# openSX70_MEROE_V7_20190605.net
KiCad netlist of a schematic drawn in EAGLE
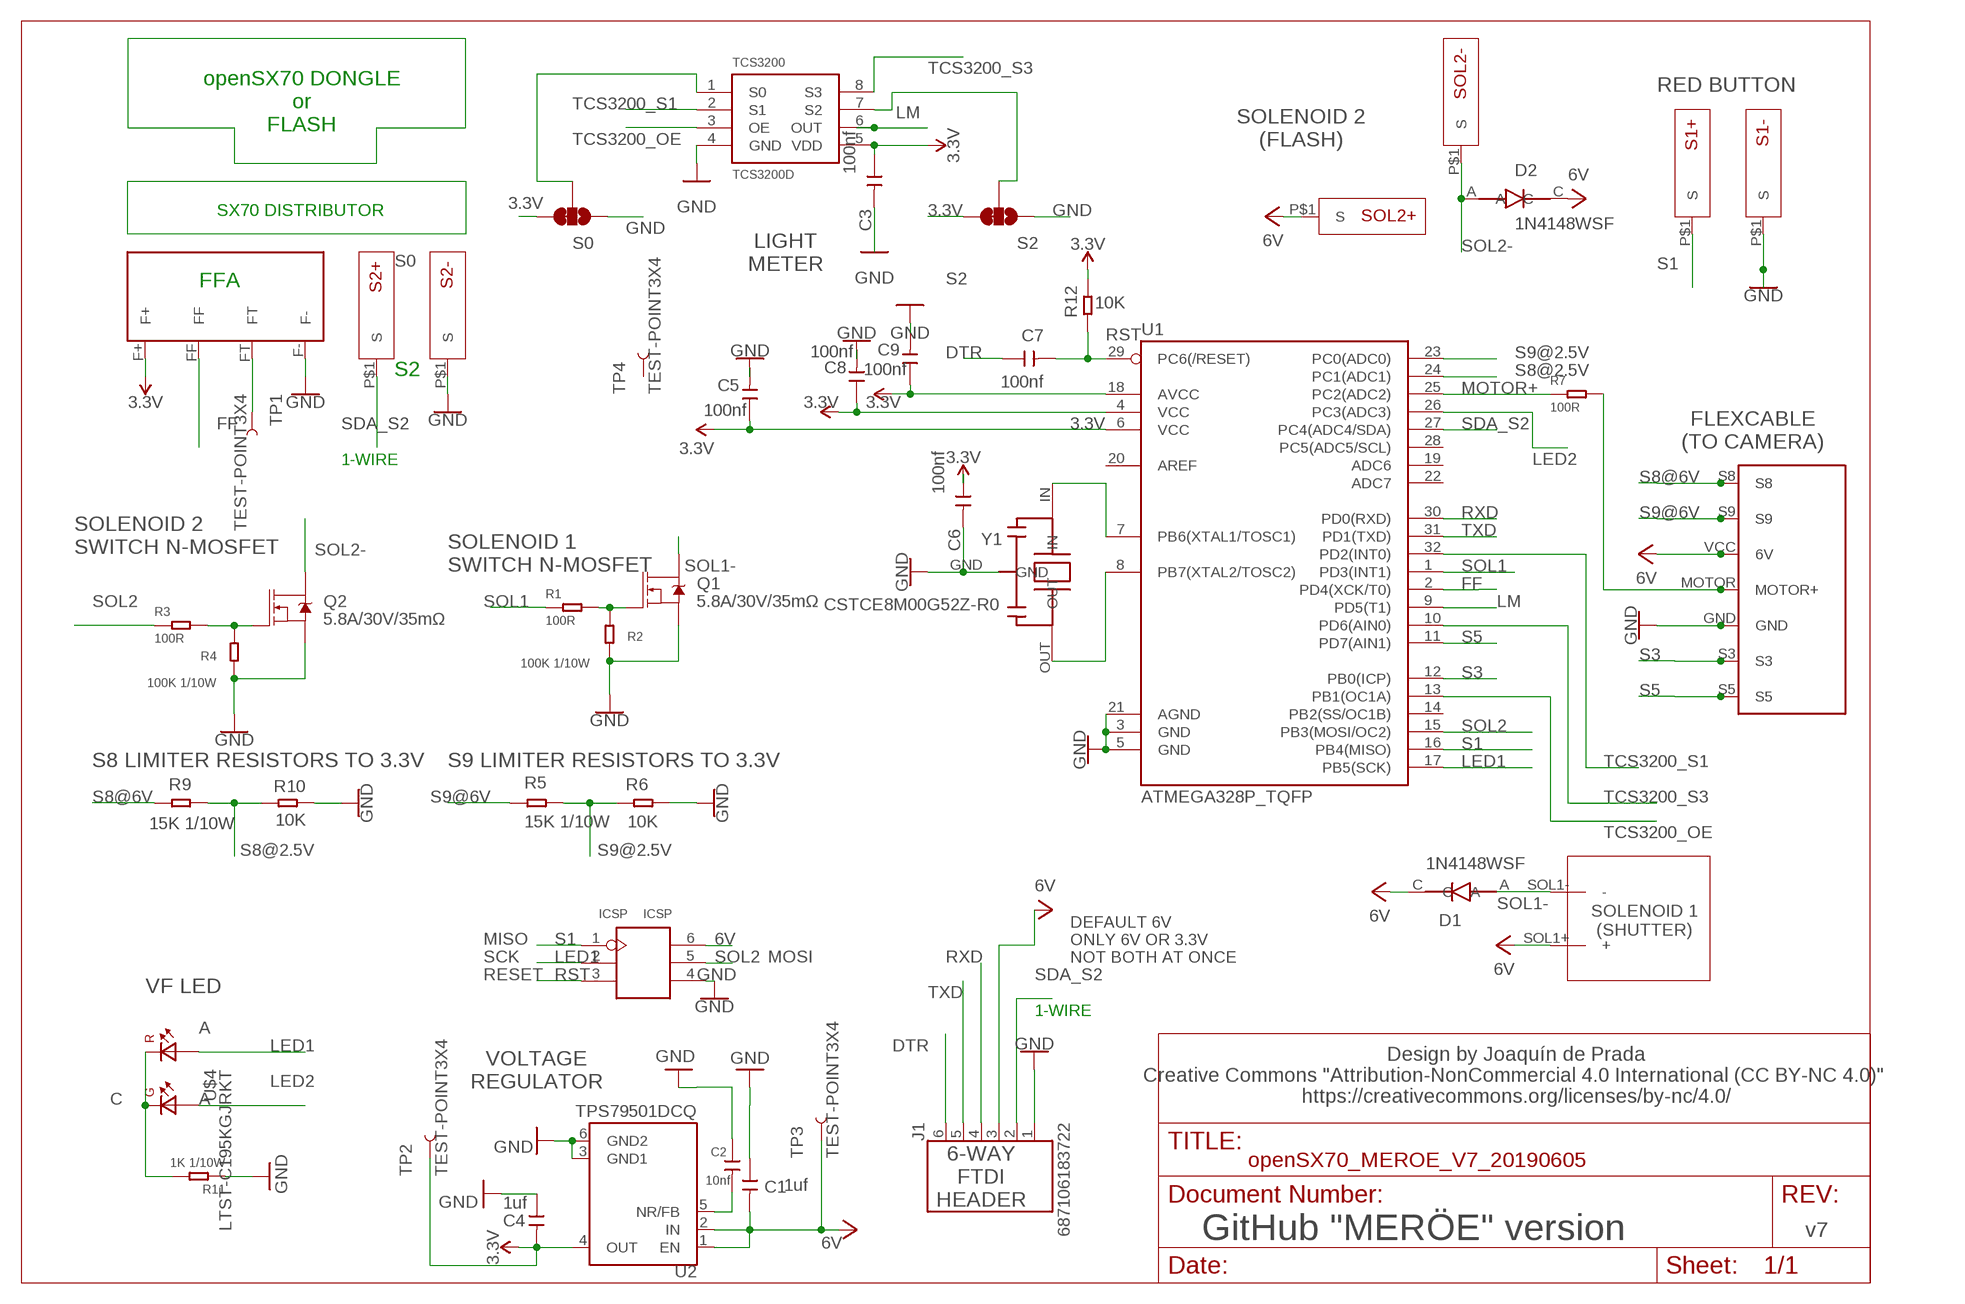
[diagram p0: schematic, sheet 1]

(export (version "E")
  (design (tool "Eeschema 10.0.6"))
  (components
    (comp (ref "C1")
      (value "1uf")
      (footprint "eagle-import:C0603")
      (fields (field (name "MPN") "CC0603KRX5R6BB106"))
      (libsource (lib "eagle-import") (part "CERAMIC-10UF-10V-10%-X5R(0603)"))
    )
    (comp (ref "C2")
      (value "10nf")
      (footprint "eagle-import:C0603")
      (fields (field (name "MPN") "CC0603KRX7R9BB104"))
      (libsource (lib "eagle-import") (part "CERAMIC-100NF-50V-10%-X7R(0603)"))
    )
    (comp (ref "C3")
      (value "100nf")
      (footprint "eagle-import:C0603")
      (fields (field (name "MPN") "CC0603KRX7R9BB104"))
      (libsource (lib "eagle-import") (part "CERAMIC-100NF-50V-10%-X7R(0603)"))
    )
    (comp (ref "C4")
      (value "1uf")
      (footprint "eagle-import:C0603")
      (fields (field (name "MPN") "CC0603KRX5R6BB106"))
      (libsource (lib "eagle-import") (part "CERAMIC-10UF-10V-10%-X5R(0603)"))
    )
    (comp (ref "C5")
      (value "100nf")
      (footprint "eagle-import:C0603")
      (fields (field (name "MPN") "CC0603KRX7R9BB104"))
      (libsource (lib "eagle-import") (part "CERAMIC-100NF-50V-10%-X7R(0603)"))
    )
    (comp (ref "C6")
      (value "100nf")
      (footprint "eagle-import:C0603")
      (fields (field (name "MPN") "CC0603KRX7R9BB104"))
      (libsource (lib "eagle-import") (part "CERAMIC-100NF-50V-10%-X7R(0603)"))
    )
    (comp (ref "C7")
      (value "100nf")
      (footprint "eagle-import:C0603")
      (fields (field (name "MPN") "CC0603KRX7R9BB104"))
      (libsource (lib "eagle-import") (part "CERAMIC-100NF-50V-10%-X7R(0603)"))
    )
    (comp (ref "C8")
      (value "100nf")
      (footprint "eagle-import:C0603")
      (fields (field (name "MPN") "CC0603KRX7R9BB104"))
      (libsource (lib "eagle-import") (part "CERAMIC-100NF-50V-10%-X7R(0603)"))
    )
    (comp (ref "C9")
      (value "100nf")
      (footprint "eagle-import:C0603")
      (fields (field (name "MPN") "CC0603KRX7R9BB104"))
      (libsource (lib "eagle-import") (part "CERAMIC-100NF-50V-10%-X7R(0603)"))
    )
    (comp (ref "D1")
      (value "1N4148WSF")
      (footprint "eagle-import:SODFL2512X100N")
      (fields (field (name "MANUFACTURER") "Fairchild Semiconductor"))
      (libsource (lib "eagle-import") (part "1N4148WS"))
    )
    (comp (ref "D2")
      (value "1N4148WSF")
      (footprint "eagle-import:SODFL2512X100N")
      (fields (field (name "MANUFACTURER") "Fairchild Semiconductor"))
      (libsource (lib "eagle-import") (part "1N4148WS"))
    )
    (comp (ref "ICSP")
      (value "ICSP")
      (footprint "eagle-import:H2X3-2.54")
      (libsource (lib "eagle-import") (part "ICSP"))
    )
    (comp (ref "J1")
      (value "687106183722")
      (footprint "eagle-import:687106183722")
      (fields (field (name "MF") "Wurth Electronics"))
      (libsource (lib "eagle-import") (part "687106183722"))
    )
    (comp (ref "Q1")
      (value "5.8A/30V/35mΩ")
      (footprint "eagle-import:SOT23-3")
      (libsource (lib "eagle-import") (part "MOSFET-NCH-AO3404A"))
    )
    (comp (ref "Q2")
      (value "5.8A/30V/35mΩ")
      (footprint "eagle-import:SOT23-3")
      (libsource (lib "eagle-import") (part "MOSFET-NCH-AO3404A"))
    )
    (comp (ref "R1")
      (value "100R")
      (footprint "eagle-import:R0603")
      (fields (field (name "MPN") "RC0603JR-07100RL"))
      (libsource (lib "eagle-import") (part "SMD-RES-100R-5%-1/10W(0603)"))
    )
    (comp (ref "R2")
      (value "100K 1/10W")
      (footprint "eagle-import:R0603")
      (fields (field (name "MPN") "RC0603JR-07100KL"))
      (libsource (lib "eagle-import") (part "SMD-RES-100K-5%-1/10W(0603)"))
    )
    (comp (ref "R3")
      (value "100R")
      (footprint "eagle-import:R0603")
      (fields (field (name "MPN") "RC0603JR-07100RL"))
      (libsource (lib "eagle-import") (part "SMD-RES-100R-5%-1/10W(0603)"))
    )
    (comp (ref "R4")
      (value "100K 1/10W")
      (footprint "eagle-import:R0603")
      (fields (field (name "MPN") "RC0603JR-07100KL"))
      (libsource (lib "eagle-import") (part "SMD-RES-100K-5%-1/10W(0603)"))
    )
    (comp (ref "R5")
      (value "15K 1/10W")
      (footprint "eagle-import:R0603")
      (fields (field (name "MPN") "RC0603FR-0715KL"))
      (libsource (lib "eagle-import") (part "SMD-RES-15K-1%-1/10W(0603)"))
    )
    (comp (ref "R6")
      (value "10K")
      (footprint "eagle-import:R0603")
      (fields (field (name "MPN") "RC0603FR-0710KL"))
      (libsource (lib "eagle-import") (part "SMD-RES-10K-1%-1/10W(0603)"))
    )
    (comp (ref "R7")
      (value "100R")
      (footprint "eagle-import:R0603")
      (fields (field (name "MPN") "RC0603JR-07100RL"))
      (libsource (lib "eagle-import") (part "SMD-RES-100R-5%-1/10W(0603)"))
    )
    (comp (ref "R9")
      (value "15K 1/10W")
      (footprint "eagle-import:R0603")
      (fields (field (name "MPN") "RC0603FR-0715KL"))
      (libsource (lib "eagle-import") (part "SMD-RES-15K-1%-1/10W(0603)"))
    )
    (comp (ref "R10")
      (value "10K")
      (footprint "eagle-import:R0603")
      (fields (field (name "MPN") "RC0603FR-0710KL"))
      (libsource (lib "eagle-import") (part "SMD-RES-10K-1%-1/10W(0603)"))
    )
    (comp (ref "R11")
      (value "1K 1/10W")
      (footprint "eagle-import:R0603")
      (fields (field (name "MPN") "RC0603JR-071KL"))
      (libsource (lib "eagle-import") (part "SMD-RES-1K-5%-1/10W(0603)"))
    )
    (comp (ref "R12")
      (value "10K")
      (footprint "eagle-import:R0603")
      (fields (field (name "MPN") "RC0603FR-0710KL"))
      (libsource (lib "eagle-import") (part "SMD-RES-10K-1%-1/10W(0603)"))
    )
    (comp (ref "S0")
      (value "S0")
      (footprint "eagle-import:SMT-JUMPER_3_1-NC_TRACE_SILK")
      (libsource (lib "eagle-import") (part "JUMPER-SMT_3_1-NC_TRACE_SILK"))
    )
    (comp (ref "S1+")
      (value "SX70-S-PAD-NEW")
      (footprint "eagle-import:SX70-S-PAD2")
      (libsource (lib "eagle-import") (part "SX70-S-PAD-NEW"))
    )
    (comp (ref "S1-")
      (value "SX70-S-PAD-NEW")
      (footprint "eagle-import:SX70-S-PAD2")
      (libsource (lib "eagle-import") (part "SX70-S-PAD-NEW"))
    )
    (comp (ref "S2")
      (value "S2")
      (footprint "eagle-import:SMT-JUMPER_3_1-NC_TRACE_SILK")
      (libsource (lib "eagle-import") (part "JUMPER-SMT_3_1-NC_TRACE_SILK"))
    )
    (comp (ref "S2+")
      (value "SX70-S-PAD-NEW")
      (footprint "eagle-import:SX70-S-PAD2")
      (libsource (lib "eagle-import") (part "SX70-S-PAD-NEW"))
    )
    (comp (ref "S2-")
      (value "SX70-S-PAD-NEW")
      (footprint "eagle-import:SX70-S-PAD2")
      (libsource (lib "eagle-import") (part "SX70-S-PAD-NEW"))
    )
    (comp (ref "SOL1")
      (value "SX70-SOLENOID1-2PADS")
      (footprint "eagle-import:SX70-SOLENOID1-2")
      (libsource (lib "eagle-import") (part "SX70-SOLENOID1-2PADS"))
    )
    (comp (ref "SOL2+")
      (value "SX70-S-PAD-NEW")
      (footprint "eagle-import:SX70-S-PAD2")
      (libsource (lib "eagle-import") (part "SX70-S-PAD-NEW"))
    )
    (comp (ref "SOL2-")
      (value "SX70-S-PAD-NEW")
      (footprint "eagle-import:SX70-S-PAD2")
      (libsource (lib "eagle-import") (part "SX70-S-PAD-NEW"))
    )
    (comp (ref "TCS3200")
      (value "TCS3200D")
      (footprint "eagle-import:SOIC8")
      (fields (field (name "MF") "ams") (field (name "MP") "TCS3200D-TR"))
      (libsource (lib "eagle-import") (part "TCS3200D"))
    )
    (comp (ref "TP1")
      (value "TEST-POINT3X4")
      (footprint "eagle-import:PAD.03X.04")
      (libsource (lib "eagle-import") (part "TEST-POINT3X4"))
    )
    (comp (ref "TP2")
      (value "TEST-POINT3X4")
      (footprint "eagle-import:PAD.03X.04")
      (libsource (lib "eagle-import") (part "TEST-POINT3X4"))
    )
    (comp (ref "TP3")
      (value "TEST-POINT3X4")
      (footprint "eagle-import:PAD.03X.04")
      (libsource (lib "eagle-import") (part "TEST-POINT3X4"))
    )
    (comp (ref "TP4")
      (value "TEST-POINT3X4")
      (footprint "eagle-import:PAD.03X.04")
      (libsource (lib "eagle-import") (part "TEST-POINT3X4"))
    )
    (comp (ref "U$1")
      (value "SX70-7-PAD")
      (footprint "eagle-import:SX70-7-PAD-PROPER")
      (libsource (lib "eagle-import") (part "SX70-7-PAD"))
    )
    (comp (ref "U$2")
      (value "FFA")
      (footprint "eagle-import:FFA-PAD-PACKAGE")
      (libsource (lib "eagle-import") (part "SX70-FFA-PAD"))
    )
    (comp (ref "U$4")
      (value "LTST-C195KGJRKT")
      (footprint "eagle-import:LTST-BILED-15X16")
      (fields (field (name "MF") "Lite-On Inc."))
      (libsource (lib "eagle-import") (part "LTST-C195KGJRKT"))
    )
    (comp (ref "U1")
      (value "ATMEGA328P_TQFP")
      (footprint "eagle-import:TQFP32-08")
      (libsource (lib "eagle-import") (part "ATMEGA328P_TQFP"))
    )
    (comp (ref "U2")
      (value "TPS79501DCQ")
      (footprint "eagle-import:SOT127P706X180-6N")
      (fields (field (name "MF") "Texas Instruments"))
      (libsource (lib "eagle-import") (part "TPS79501DCQ"))
    )
    (comp (ref "Y1")
      (value "CSTCE8M00G52Z-R0")
      (footprint "eagle-import:CFP95P160X100-3N")
      (fields (field (name "MF") "Murata") (field (name "MP") "CSTCE16M0V53-R0"))
      (libsource (lib "eagle-import") (part "CSTCE16M0V53-R0"))
    )
  )
  (nets
    (net (code "1") (name "/DTR") (class "Default")
      (node (ref "C7") (pin "1") (pinfunction "1_1") (pintype "passive"))
      (node (ref "J1") (pin "6") (pinfunction "1_6") (pintype "passive"))
    )
    (net (code "2") (name "/FF") (class "Default")
      (node (ref "U$2") (pin "FF") (pinfunction "FF_FF") (pintype "bidirectional"))
      (node (ref "U1") (pin "2") (pinfunction "PD4(XCK/T0)_2") (pintype "bidirectional"))
    )
    (net (code "3") (name "/LED1") (class "Default")
      (node (ref "ICSP") (pin "2") (pinfunction "SCK_2") (pintype "bidirectional"))
      (node (ref "U$4") (pin "P$2") (pinfunction "A2_P$2") (pintype "passive"))
      (node (ref "U1") (pin "17") (pinfunction "PB5(SCK)_17") (pintype "bidirectional"))
    )
    (net (code "4") (name "/LED2") (class "Default")
      (node (ref "U$4") (pin "P$1") (pinfunction "A1_P$1") (pintype "passive"))
      (node (ref "U1") (pin "26") (pinfunction "PC3(ADC3)_26") (pintype "bidirectional"))
    )
    (net (code "5") (name "/LM") (class "Default")
      (node (ref "TCS3200") (pin "6") (pinfunction "OUT_6") (pintype "bidirectional"))
      (node (ref "U1") (pin "9") (pinfunction "PD5(T1)_9") (pintype "bidirectional"))
    )
    (net (code "6") (name "/MOTOR+") (class "Default")
      (node (ref "R7") (pin "1") (pinfunction "1_1") (pintype "passive"))
      (node (ref "U1") (pin "25") (pinfunction "PC2(ADC2)_25") (pintype "bidirectional"))
    )
    (net (code "7") (name "/RST") (class "Default")
      (node (ref "C7") (pin "2") (pinfunction "2_2") (pintype "passive"))
      (node (ref "ICSP") (pin "3") (pinfunction "RST_3") (pintype "bidirectional"))
      (node (ref "R12") (pin "1") (pinfunction "1_1") (pintype "passive"))
      (node (ref "U1") (pin "29") (pinfunction "PC6(/RESET)_29") (pintype "bidirectional"))
    )
    (net (code "8") (name "/RXD") (class "Default")
      (node (ref "J1") (pin "4") (pinfunction "3_4") (pintype "passive"))
      (node (ref "U1") (pin "30") (pinfunction "PD0(RXD)_30") (pintype "bidirectional"))
    )
    (net (code "9") (name "/S1") (class "Default")
      (node (ref "ICSP") (pin "1") (pinfunction "MISO_1") (pintype "bidirectional"))
      (node (ref "S1+") (pin "P$1") (pinfunction "S_P$1") (pintype "bidirectional"))
      (node (ref "U1") (pin "16") (pinfunction "PB4(MISO)_16") (pintype "bidirectional"))
    )
    (net (code "10") (name "/S3") (class "Default")
      (node (ref "U$1") (pin "S3") (pinfunction "S3_S3") (pintype "bidirectional"))
      (node (ref "U1") (pin "12") (pinfunction "PB0(ICP)_12") (pintype "bidirectional"))
    )
    (net (code "11") (name "/S5") (class "Default")
      (node (ref "U$1") (pin "S5") (pinfunction "S5_S5") (pintype "bidirectional"))
      (node (ref "U1") (pin "11") (pinfunction "PD7(AIN1)_11") (pintype "bidirectional"))
    )
    (net (code "12") (name "/S8@2.5V") (class "Default")
      (node (ref "R10") (pin "1") (pinfunction "1_1") (pintype "passive"))
      (node (ref "R9") (pin "2") (pinfunction "2_2") (pintype "passive"))
      (node (ref "U1") (pin "24") (pinfunction "PC1(ADC1)_24") (pintype "bidirectional"))
    )
    (net (code "13") (name "/S8@6V") (class "Default")
      (node (ref "R9") (pin "1") (pinfunction "1_1") (pintype "passive"))
      (node (ref "U$1") (pin "S8") (pinfunction "S8_S8") (pintype "bidirectional"))
    )
    (net (code "14") (name "/S9@2.5V") (class "Default")
      (node (ref "R5") (pin "2") (pinfunction "2_2") (pintype "passive"))
      (node (ref "R6") (pin "1") (pinfunction "1_1") (pintype "passive"))
      (node (ref "U1") (pin "23") (pinfunction "PC0(ADC0)_23") (pintype "bidirectional"))
    )
    (net (code "15") (name "/S9@6V") (class "Default")
      (node (ref "R5") (pin "1") (pinfunction "1_1") (pintype "passive"))
      (node (ref "U$1") (pin "S9") (pinfunction "S9_S9") (pintype "bidirectional"))
    )
    (net (code "16") (name "/SDA_S2") (class "Default")
      (node (ref "J1") (pin "2") (pinfunction "5_2") (pintype "passive"))
      (node (ref "S2+") (pin "P$1") (pinfunction "S_P$1") (pintype "bidirectional"))
      (node (ref "U1") (pin "27") (pinfunction "PC4(ADC4/SDA)_27") (pintype "bidirectional"))
    )
    (net (code "17") (name "/SOL1") (class "Default")
      (node (ref "R1") (pin "1") (pinfunction "1_1") (pintype "passive"))
      (node (ref "U1") (pin "1") (pinfunction "PD3(INT1)_1") (pintype "bidirectional"))
    )
    (net (code "18") (name "/SOL1-") (class "Default")
      (node (ref "D1") (pin "A") (pinfunction "A_A") (pintype "passive"))
      (node (ref "Q1") (pin "3") (pinfunction "D_3") (pintype "bidirectional"))
      (node (ref "SOL1") (pin "SOL1-") (pinfunction "-_SOL1-") (pintype "bidirectional"))
    )
    (net (code "19") (name "/SOL2") (class "Default")
      (node (ref "ICSP") (pin "5") (pinfunction "MOSI_5") (pintype "bidirectional"))
      (node (ref "R3") (pin "1") (pinfunction "1_1") (pintype "passive"))
      (node (ref "U1") (pin "15") (pinfunction "PB3(MOSI/OC2)_15") (pintype "bidirectional"))
    )
    (net (code "20") (name "/SOL2-") (class "Default")
      (node (ref "D2") (pin "A") (pinfunction "A_A") (pintype "passive"))
      (node (ref "Q2") (pin "3") (pinfunction "D_3") (pintype "bidirectional"))
      (node (ref "SOL2-") (pin "P$1") (pinfunction "S_P$1") (pintype "bidirectional"))
    )
    (net (code "21") (name "/TCS3200_OE") (class "Default")
      (node (ref "TCS3200") (pin "3") (pinfunction "OE_3") (pintype "bidirectional"))
      (node (ref "U1") (pin "13") (pinfunction "PB1(OC1A)_13") (pintype "bidirectional"))
    )
    (net (code "22") (name "/TCS3200_S1") (class "Default")
      (node (ref "TCS3200") (pin "2") (pinfunction "S1_2") (pintype "bidirectional"))
      (node (ref "U1") (pin "32") (pinfunction "PD2(INT0)_32") (pintype "bidirectional"))
    )
    (net (code "23") (name "/TCS3200_S3") (class "Default")
      (node (ref "TCS3200") (pin "8") (pinfunction "S3_8") (pintype "bidirectional"))
      (node (ref "U1") (pin "10") (pinfunction "PD6(AIN0)_10") (pintype "bidirectional"))
    )
    (net (code "24") (name "/TXD") (class "Default")
      (node (ref "J1") (pin "5") (pinfunction "2_5") (pintype "passive"))
      (node (ref "U1") (pin "31") (pinfunction "PD1(TXD)_31") (pintype "bidirectional"))
    )
    (net (code "25") (name "3.3V") (class "Default")
      (node (ref "C3") (pin "1") (pinfunction "1_1") (pintype "passive"))
      (node (ref "C4") (pin "2") (pinfunction "2_2") (pintype "passive"))
      (node (ref "C5") (pin "1") (pinfunction "1_1") (pintype "passive"))
      (node (ref "C6") (pin "1") (pinfunction "1_1") (pintype "passive"))
      (node (ref "C8") (pin "1") (pinfunction "1_1") (pintype "passive"))
      (node (ref "C9") (pin "1") (pinfunction "1_1") (pintype "passive"))
      (node (ref "R12") (pin "2") (pinfunction "2_2") (pintype "passive"))
      (node (ref "S0") (pin "3") (pinfunction "3_3") (pintype "passive"))
      (node (ref "S2") (pin "3") (pinfunction "3_3") (pintype "passive"))
      (node (ref "TCS3200") (pin "5") (pinfunction "VDD_5") (pintype "bidirectional"))
      (node (ref "TP2") (pin "P$1") (pinfunction "1_P$1") (pintype "bidirectional"))
      (node (ref "U$2") (pin "F+") (pinfunction "F+_F+") (pintype "bidirectional"))
      (node (ref "U1") (pin "18") (pinfunction "AVCC_18") (pintype "bidirectional"))
      (node (ref "U1") (pin "4") (pinfunction "VCC_4") (pintype "bidirectional"))
      (node (ref "U1") (pin "6") (pinfunction "VCC_6") (pintype "bidirectional"))
      (node (ref "U2") (pin "4") (pinfunction "OUT_4") (pintype "output"))
    )
    (net (code "26") (name "6V") (class "Default")
      (node (ref "C1") (pin "2") (pinfunction "2_2") (pintype "passive"))
      (node (ref "D1") (pin "C") (pinfunction "C_C") (pintype "passive"))
      (node (ref "D2") (pin "C") (pinfunction "C_C") (pintype "passive"))
      (node (ref "ICSP") (pin "6") (pinfunction "VCC_6") (pintype "bidirectional"))
      (node (ref "J1") (pin "3") (pinfunction "4_3") (pintype "passive"))
      (node (ref "SOL1") (pin "SOL1+") (pinfunction "+_SOL1+") (pintype "bidirectional"))
      (node (ref "SOL2+") (pin "P$1") (pinfunction "S_P$1") (pintype "bidirectional"))
      (node (ref "TP3") (pin "P$1") (pinfunction "1_P$1") (pintype "bidirectional"))
      (node (ref "U$1") (pin "VCC") (pinfunction "6V_VCC") (pintype "bidirectional"))
      (node (ref "U2") (pin "1") (pinfunction "EN_1") (pintype "input"))
      (node (ref "U2") (pin "2") (pinfunction "IN_2") (pintype "input"))
    )
    (net (code "27") (name "GND") (class "Default")
      (node (ref "C1") (pin "1") (pinfunction "1_1") (pintype "passive"))
      (node (ref "C2") (pin "1") (pinfunction "1_1") (pintype "passive"))
      (node (ref "C3") (pin "2") (pinfunction "2_2") (pintype "passive"))
      (node (ref "C4") (pin "1") (pinfunction "1_1") (pintype "passive"))
      (node (ref "C5") (pin "2") (pinfunction "2_2") (pintype "passive"))
      (node (ref "C6") (pin "2") (pinfunction "2_2") (pintype "passive"))
      (node (ref "C8") (pin "2") (pinfunction "2_2") (pintype "passive"))
      (node (ref "C9") (pin "2") (pinfunction "2_2") (pintype "passive"))
      (node (ref "ICSP") (pin "4") (pinfunction "GND_4") (pintype "bidirectional"))
      (node (ref "J1") (pin "1") (pinfunction "6_1") (pintype "passive"))
      (node (ref "Q1") (pin "2") (pinfunction "S_2") (pintype "bidirectional"))
      (node (ref "Q2") (pin "2") (pinfunction "S_2") (pintype "bidirectional"))
      (node (ref "R10") (pin "2") (pinfunction "2_2") (pintype "passive"))
      (node (ref "R11") (pin "1") (pinfunction "1_1") (pintype "passive"))
      (node (ref "R2") (pin "1") (pinfunction "1_1") (pintype "passive"))
      (node (ref "R4") (pin "1") (pinfunction "1_1") (pintype "passive"))
      (node (ref "R6") (pin "2") (pinfunction "2_2") (pintype "passive"))
      (node (ref "S0") (pin "1") (pinfunction "1_1") (pintype "passive"))
      (node (ref "S1-") (pin "P$1") (pinfunction "S_P$1") (pintype "bidirectional"))
      (node (ref "S2") (pin "1") (pinfunction "1_1") (pintype "passive"))
      (node (ref "S2-") (pin "P$1") (pinfunction "S_P$1") (pintype "bidirectional"))
      (node (ref "TCS3200") (pin "4") (pinfunction "GND_4") (pintype "bidirectional"))
      (node (ref "U$1") (pin "GND") (pinfunction "GND_GND") (pintype "bidirectional"))
      (node (ref "U$2") (pin "F-") (pinfunction "F-_F-") (pintype "bidirectional"))
      (node (ref "U1") (pin "21") (pinfunction "AGND_21") (pintype "bidirectional"))
      (node (ref "U1") (pin "3") (pinfunction "GND_3") (pintype "bidirectional"))
      (node (ref "U1") (pin "5") (pinfunction "GND_5") (pintype "bidirectional"))
      (node (ref "U2") (pin "3") (pinfunction "GND1_3") (pintype "power_in"))
      (node (ref "U2") (pin "6") (pinfunction "GND2_6") (pintype "power_in"))
      (node (ref "Y1") (pin "GND") (pinfunction "GND_GND") (pintype "passive"))
    )
    (net (code "28") (name "Net-(Q1-G)") (class "Default")
      (node (ref "Q1") (pin "1") (pinfunction "G_1") (pintype "bidirectional"))
      (node (ref "R1") (pin "2") (pinfunction "2_2") (pintype "passive"))
      (node (ref "R2") (pin "2") (pinfunction "2_2") (pintype "passive"))
    )
    (net (code "29") (name "Net-(Q2-G)") (class "Default")
      (node (ref "Q2") (pin "1") (pinfunction "G_1") (pintype "bidirectional"))
      (node (ref "R3") (pin "2") (pinfunction "2_2") (pintype "passive"))
      (node (ref "R4") (pin "2") (pinfunction "2_2") (pintype "passive"))
    )
    (net (code "30") (name "Net-(TCS3200-S0)") (class "Default")
      (node (ref "S0") (pin "2") (pinfunction "2_2") (pintype "passive"))
      (node (ref "TCS3200") (pin "1") (pinfunction "S0_1") (pintype "bidirectional"))
    )
    (net (code "31") (name "Net-(TCS3200-S2)") (class "Default")
      (node (ref "S2") (pin "2") (pinfunction "2_2") (pintype "passive"))
      (node (ref "TCS3200") (pin "7") (pinfunction "S2_7") (pintype "bidirectional"))
    )
    (net (code "32") (name "Net-(TP1-1)") (class "Default")
      (node (ref "TP1") (pin "P$1") (pinfunction "1_P$1") (pintype "bidirectional"))
      (node (ref "U$2") (pin "FT") (pinfunction "FT_FT") (pintype "bidirectional"))
    )
    (net (code "33") (name "Net-(U$1-MOTOR+)") (class "Default")
      (node (ref "R7") (pin "2") (pinfunction "2_2") (pintype "passive"))
      (node (ref "U$1") (pin "MOTOR") (pinfunction "MOTOR+_MOTOR") (pintype "bidirectional"))
    )
    (net (code "34") (name "Net-(U$4-K1)") (class "Default")
      (node (ref "R11") (pin "2") (pinfunction "2_2") (pintype "passive"))
      (node (ref "U$4") (pin "P$3") (pinfunction "K1_P$3") (pintype "passive"))
      (node (ref "U$4") (pin "P$4") (pinfunction "K2_P$4") (pintype "passive"))
    )
    (net (code "35") (name "Net-(U1-PB6(XTAL1{slash}TOSC1))") (class "Default")
      (node (ref "U1") (pin "7") (pinfunction "PB6(XTAL1/TOSC1)_7") (pintype "bidirectional"))
      (node (ref "Y1") (pin "IN") (pinfunction "IN_IN") (pintype "input"))
    )
    (net (code "36") (name "Net-(U1-PB7(XTAL2{slash}TOSC2))") (class "Default")
      (node (ref "U1") (pin "8") (pinfunction "PB7(XTAL2/TOSC2)_8") (pintype "bidirectional"))
      (node (ref "Y1") (pin "OUT") (pinfunction "OUT_OUT") (pintype "output"))
    )
    (net (code "37") (name "Net-(U2-NR{slash}FB)") (class "Default")
      (node (ref "C2") (pin "2") (pinfunction "2_2") (pintype "passive"))
      (node (ref "U2") (pin "5") (pinfunction "NR/FB_5") (pintype "input"))
    )
    (net (code "38") (name "unconnected-(TP4-1-PadP$1)") (class "Default")
      (node (ref "TP4") (pin "P$1") (pinfunction "1_P$1") (pintype "bidirectional"))
    )
    (net (code "39") (name "unconnected-(U1-ADC6-Pad19)") (class "Default")
      (node (ref "U1") (pin "19") (pinfunction "ADC6_19") (pintype "bidirectional"))
    )
    (net (code "40") (name "unconnected-(U1-ADC7-Pad22)") (class "Default")
      (node (ref "U1") (pin "22") (pinfunction "ADC7_22") (pintype "bidirectional"))
    )
    (net (code "41") (name "unconnected-(U1-AREF-Pad20)") (class "Default")
      (node (ref "U1") (pin "20") (pinfunction "AREF_20") (pintype "bidirectional"))
    )
    (net (code "42") (name "unconnected-(U1-PB2(SS{slash}OC1B)-Pad14)") (class "Default")
      (node (ref "U1") (pin "14") (pinfunction "PB2(SS/OC1B)_14") (pintype "bidirectional"))
    )
    (net (code "43") (name "unconnected-(U1-PC5(ADC5{slash}SCL)-Pad28)") (class "Default")
      (node (ref "U1") (pin "28") (pinfunction "PC5(ADC5/SCL)_28") (pintype "bidirectional"))
    )
  )
)
